# Sheet2.net
KiCad netlist of a schematic drawn in Altium Designer
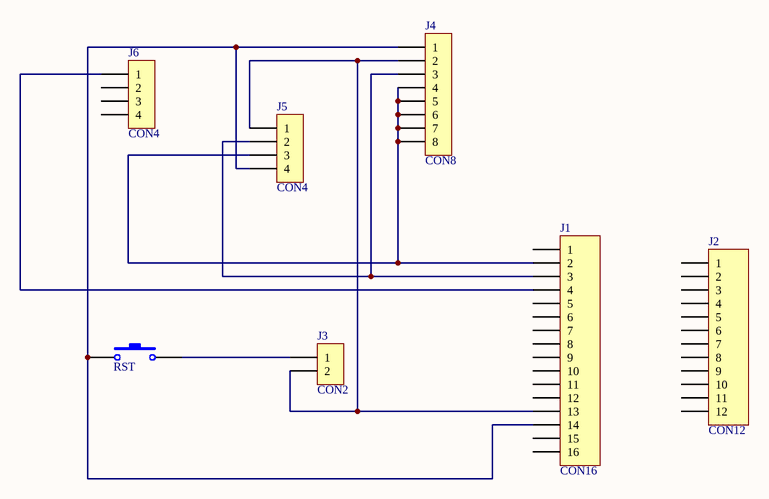
[diagram p0: Sheet2.SchDoc]

(export (version "E")
  (design (tool "Eeschema 10.0.6"))
  (components
    (comp (ref "J1")
      (value "CON16")
      (footprint "HDR1X16")
      (description "Connector")
      (libsource (lib "插件") (part "CON16"))
    )
    (comp (ref "J2")
      (value "CON12")
      (footprint "HDR1X12")
      (description "Connector")
      (libsource (lib "插件") (part "CON12"))
    )
    (comp (ref "J3")
      (value "CON2")
      (footprint "HDR1X2")
      (description "Connector")
      (libsource (lib "插件") (part "CON2"))
    )
    (comp (ref "J4")
      (value "CON8")
      (footprint "HDR1X8")
      (description "Connector")
      (libsource (lib "插件") (part "CON8"))
    )
    (comp (ref "J5")
      (value "CON4")
      (footprint "HDR1X4")
      (description "Connector")
      (libsource (lib "插件") (part "CON4"))
    )
    (comp (ref "J6")
      (value "CON4")
      (footprint "HDR1X4")
      (description "Connector")
      (libsource (lib "插件") (part "CON4"))
    )
    (comp (ref "RST")
      (value "SW-PB")
      (footprint "KEY-K2")
      (description "Switch")
      (fields (field (name "MANUFACTURER") "Generic Components"))
      (libsource (lib "EPC144_new") (part "SW-PB"))
    )
  )
  (nets
    (net (code "1") (name "Net-(J1-Pad2)") (class "Default")
      (node (ref "J1") (pin "2") (pinfunction "2_2") (pintype "passive"))
      (node (ref "J4") (pin "4") (pinfunction "4_4") (pintype "passive"))
      (node (ref "J4") (pin "5") (pinfunction "5_5") (pintype "passive"))
      (node (ref "J4") (pin "6") (pinfunction "6_6") (pintype "passive"))
      (node (ref "J4") (pin "7") (pinfunction "7_7") (pintype "passive"))
      (node (ref "J4") (pin "8") (pinfunction "8_8") (pintype "passive"))
      (node (ref "J5") (pin "3") (pinfunction "3_3") (pintype "passive"))
    )
    (net (code "2") (name "Net-(J1-Pad3)") (class "Default")
      (node (ref "J1") (pin "3") (pinfunction "3_3") (pintype "passive"))
      (node (ref "J4") (pin "3") (pinfunction "3_3") (pintype "passive"))
      (node (ref "J5") (pin "2") (pinfunction "2_2") (pintype "passive"))
    )
    (net (code "3") (name "Net-(J1-Pad4)") (class "Default")
      (node (ref "J1") (pin "4") (pinfunction "4_4") (pintype "passive"))
      (node (ref "J6") (pin "1") (pinfunction "1_1") (pintype "passive"))
    )
    (net (code "4") (name "Net-(J1-Pad13)") (class "Default")
      (node (ref "J1") (pin "13") (pinfunction "13_13") (pintype "passive"))
      (node (ref "J3") (pin "2") (pinfunction "2_2") (pintype "passive"))
      (node (ref "J4") (pin "2") (pinfunction "2_2") (pintype "passive"))
      (node (ref "J5") (pin "1") (pinfunction "1_1") (pintype "passive"))
    )
    (net (code "5") (name "Net-(J1-Pad14)") (class "Default")
      (node (ref "J1") (pin "14") (pinfunction "14_14") (pintype "passive"))
      (node (ref "J4") (pin "1") (pinfunction "1_1") (pintype "passive"))
      (node (ref "J5") (pin "4") (pinfunction "4_4") (pintype "passive"))
      (node (ref "RST") (pin "1") (pinfunction "1_1") (pintype "passive"))
    )
    (net (code "6") (name "Net-(J3-Pad1)") (class "Default")
      (node (ref "J3") (pin "1") (pinfunction "1_1") (pintype "passive"))
      (node (ref "RST") (pin "2") (pinfunction "2_2") (pintype "passive"))
    )
    (net (code "7") (name "unconnected-(J1-Pad1)") (class "Default")
      (node (ref "J1") (pin "1") (pinfunction "1_1") (pintype "passive"))
    )
    (net (code "8") (name "unconnected-(J1-Pad5)") (class "Default")
      (node (ref "J1") (pin "5") (pinfunction "5_5") (pintype "passive"))
    )
    (net (code "9") (name "unconnected-(J1-Pad6)") (class "Default")
      (node (ref "J1") (pin "6") (pinfunction "6_6") (pintype "passive"))
    )
    (net (code "10") (name "unconnected-(J1-Pad7)") (class "Default")
      (node (ref "J1") (pin "7") (pinfunction "7_7") (pintype "passive"))
    )
    (net (code "11") (name "unconnected-(J1-Pad8)") (class "Default")
      (node (ref "J1") (pin "8") (pinfunction "8_8") (pintype "passive"))
    )
    (net (code "12") (name "unconnected-(J1-Pad9)") (class "Default")
      (node (ref "J1") (pin "9") (pinfunction "9_9") (pintype "passive"))
    )
    (net (code "13") (name "unconnected-(J1-Pad10)") (class "Default")
      (node (ref "J1") (pin "10") (pinfunction "10_10") (pintype "passive"))
    )
    (net (code "14") (name "unconnected-(J1-Pad11)") (class "Default")
      (node (ref "J1") (pin "11") (pinfunction "11_11") (pintype "passive"))
    )
    (net (code "15") (name "unconnected-(J1-Pad12)") (class "Default")
      (node (ref "J1") (pin "12") (pinfunction "12_12") (pintype "passive"))
    )
    (net (code "16") (name "unconnected-(J1-Pad15)") (class "Default")
      (node (ref "J1") (pin "15") (pinfunction "15_15") (pintype "passive"))
    )
    (net (code "17") (name "unconnected-(J1-Pad16)") (class "Default")
      (node (ref "J1") (pin "16") (pinfunction "16_16") (pintype "passive"))
    )
    (net (code "18") (name "unconnected-(J2-Pad1)") (class "Default")
      (node (ref "J2") (pin "1") (pinfunction "1_1") (pintype "passive"))
    )
    (net (code "19") (name "unconnected-(J2-Pad2)") (class "Default")
      (node (ref "J2") (pin "2") (pinfunction "2_2") (pintype "passive"))
    )
    (net (code "20") (name "unconnected-(J2-Pad3)") (class "Default")
      (node (ref "J2") (pin "3") (pinfunction "3_3") (pintype "passive"))
    )
    (net (code "21") (name "unconnected-(J2-Pad4)") (class "Default")
      (node (ref "J2") (pin "4") (pinfunction "4_4") (pintype "passive"))
    )
    (net (code "22") (name "unconnected-(J2-Pad5)") (class "Default")
      (node (ref "J2") (pin "5") (pinfunction "5_5") (pintype "passive"))
    )
    (net (code "23") (name "unconnected-(J2-Pad6)") (class "Default")
      (node (ref "J2") (pin "6") (pinfunction "6_6") (pintype "passive"))
    )
    (net (code "24") (name "unconnected-(J2-Pad7)") (class "Default")
      (node (ref "J2") (pin "7") (pinfunction "7_7") (pintype "passive"))
    )
    (net (code "25") (name "unconnected-(J2-Pad8)") (class "Default")
      (node (ref "J2") (pin "8") (pinfunction "8_8") (pintype "passive"))
    )
    (net (code "26") (name "unconnected-(J2-Pad9)") (class "Default")
      (node (ref "J2") (pin "9") (pinfunction "9_9") (pintype "passive"))
    )
    (net (code "27") (name "unconnected-(J2-Pad10)") (class "Default")
      (node (ref "J2") (pin "10") (pinfunction "10_10") (pintype "passive"))
    )
    (net (code "28") (name "unconnected-(J2-Pad11)") (class "Default")
      (node (ref "J2") (pin "11") (pinfunction "11_11") (pintype "passive"))
    )
    (net (code "29") (name "unconnected-(J2-Pad12)") (class "Default")
      (node (ref "J2") (pin "12") (pinfunction "12_12") (pintype "passive"))
    )
    (net (code "30") (name "unconnected-(J6-Pad2)") (class "Default")
      (node (ref "J6") (pin "2") (pinfunction "2_2") (pintype "passive"))
    )
    (net (code "31") (name "unconnected-(J6-Pad3)") (class "Default")
      (node (ref "J6") (pin "3") (pinfunction "3_3") (pintype "passive"))
    )
    (net (code "32") (name "unconnected-(J6-Pad4)") (class "Default")
      (node (ref "J6") (pin "4") (pinfunction "4_4") (pintype "passive"))
    )
  )
)
